# light_detector_v2_3.net
KiCad netlist of a schematic drawn in EAGLE
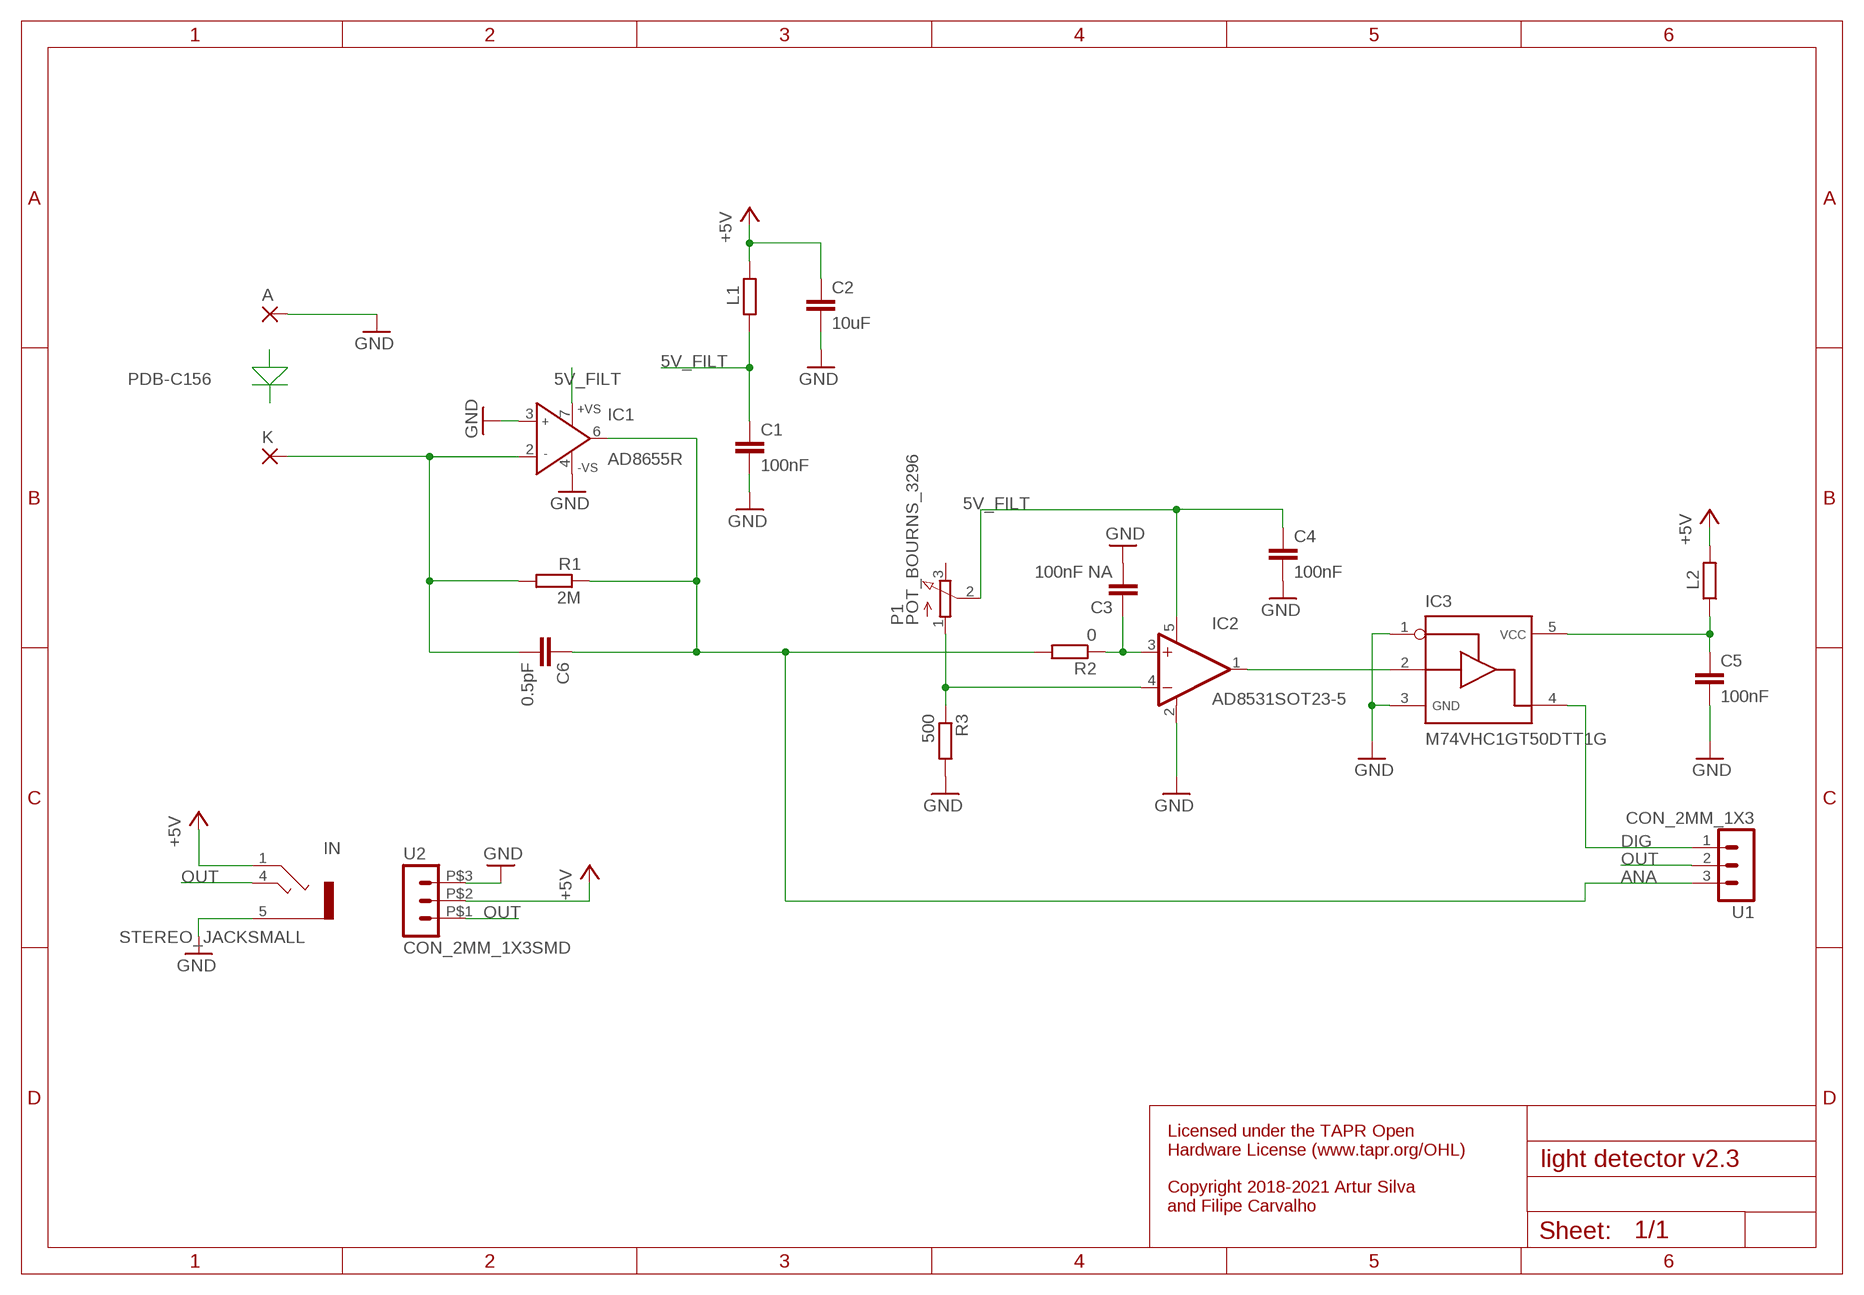
[diagram p0: schematic, sheet 1]

(export (version "E")
  (design (tool "Eeschema 10.0.6"))
  (components
    (comp (ref "A")
      (value "1,6/0,8")
      (footprint "eagle-import:1,6_0,8")
      (libsource (lib "eagle-import") (part "1,6/0,8"))
    )
    (comp (ref "C1")
      (value "100nF")
      (footprint "eagle-import:C0402")
      (libsource (lib "eagle-import") (part "C-EUC0402"))
    )
    (comp (ref "C2")
      (value "10uF")
      (footprint "eagle-import:C0603")
      (libsource (lib "eagle-import") (part "C-EUC0603"))
    )
    (comp (ref "C3")
      (value "100nF NA")
      (footprint "eagle-import:C0402")
      (libsource (lib "eagle-import") (part "C-EUC0402"))
    )
    (comp (ref "C4")
      (value "100nF")
      (footprint "eagle-import:C0402")
      (libsource (lib "eagle-import") (part "C-EUC0402"))
    )
    (comp (ref "C5")
      (value "100nF")
      (footprint "eagle-import:C0402")
      (libsource (lib "eagle-import") (part "C-EUC0402"))
    )
    (comp (ref "C6")
      (value "0.5pF")
      (footprint "eagle-import:C0402")
      (libsource (lib "eagle-import") (part "C-EUC0402"))
    )
    (comp (ref "IC1")
      (value "AD8655R")
      (footprint "eagle-import:SO8")
      (fields (field (name "MF") "ALTERA CORPORATION") (field (name "MPN") "AD8655ARMZ-REEL"))
      (libsource (lib "eagle-import") (part "AD8655R"))
    )
    (comp (ref "IC2")
      (value "AD8531SOT23-5")
      (footprint "eagle-import:SOT23-5")
      (libsource (lib "eagle-import") (part "AD8531SOT23-5"))
    )
    (comp (ref "IC3")
      (value "M74VHC1GT50DTT1G")
      (footprint "eagle-import:SOT23-5")
      (libsource (lib "eagle-import") (part "SN74LVC1G125"))
    )
    (comp (ref "IN")
      (value "STEREO_JACKSMALL")
      (footprint "eagle-import:35RASMT2BHNTRX_")
      (libsource (lib "eagle-import") (part "STEREO_JACKSMALL"))
    )
    (comp (ref "K")
      (value "1,6/0,8")
      (footprint "eagle-import:1,6_0,8")
      (libsource (lib "eagle-import") (part "1,6/0,8"))
    )
    (comp (ref "L1")
      (value "1k@100M")
      (footprint "eagle-import:R0402")
      (libsource (lib "eagle-import") (part "R-EU_R0402"))
    )
    (comp (ref "L2")
      (value "1k@100M")
      (footprint "eagle-import:R0402")
      (libsource (lib "eagle-import") (part "R-EU_R0402"))
    )
    (comp (ref "P1")
      (value "POT_BOURNS_3296")
      (footprint "eagle-import:POT_BOURNS_3296P")
      (libsource (lib "eagle-import") (part "POT_BOURNS_3296"))
    )
    (comp (ref "R1")
      (value "2M")
      (footprint "eagle-import:R0402")
      (libsource (lib "eagle-import") (part "R-EU_R0402"))
    )
    (comp (ref "R2")
      (value "0")
      (footprint "eagle-import:R0402")
      (libsource (lib "eagle-import") (part "R-EU_R0402"))
    )
    (comp (ref "R3")
      (value "500")
      (footprint "eagle-import:R0402")
      (libsource (lib "eagle-import") (part "R-EU_R0402"))
    )
    (comp (ref "U1")
      (value "CON_2MM_1X3")
      (footprint "eagle-import:CON_2MM_1X3")
      (libsource (lib "eagle-import") (part "CON_2MM_1X3"))
    )
    (comp (ref "U2")
      (value "CON_2MM_1X3SMD")
      (footprint "eagle-import:CON_2MM_1X3_SMD")
      (libsource (lib "eagle-import") (part "CON_2MM_1X3SMD"))
    )
  )
  (nets
    (net (code "1") (name "+5V") (class "Default")
      (node (ref "C2") (pin "1") (pinfunction "1_1") (pintype "passive"))
      (node (ref "IN") (pin "1") (pinfunction "1_1") (pintype "passive"))
      (node (ref "L1") (pin "1") (pinfunction "1_1") (pintype "passive"))
      (node (ref "L2") (pin "2") (pinfunction "2_2") (pintype "passive"))
      (node (ref "U2") (pin "P$2") (pinfunction "2_P$2") (pintype "passive"))
    )
    (net (code "2") (name "/5V_FILT") (class "Default")
      (node (ref "C1") (pin "1") (pinfunction "1_1") (pintype "passive"))
      (node (ref "C4") (pin "1") (pinfunction "1_1") (pintype "passive"))
      (node (ref "IC1") (pin "7") (pinfunction "+VS_7") (pintype "input"))
      (node (ref "IC2") (pin "5") (pinfunction "V+_5") (pintype "power_in"))
      (node (ref "L1") (pin "2") (pinfunction "2_2") (pintype "passive"))
      (node (ref "P1") (pin "2") (pinfunction "S_2") (pintype "passive"))
    )
    (net (code "3") (name "/ANA") (class "Default")
      (node (ref "C6") (pin "1") (pinfunction "1_1") (pintype "passive"))
      (node (ref "IC1") (pin "6") (pinfunction "OUT_6") (pintype "output"))
      (node (ref "R1") (pin "1") (pinfunction "1_1") (pintype "passive"))
      (node (ref "R2") (pin "2") (pinfunction "2_2") (pintype "passive"))
      (node (ref "U1") (pin "3") (pinfunction "3_3") (pintype "passive"))
    )
    (net (code "4") (name "/DIG") (class "Default")
      (node (ref "IC3") (pin "4") (pinfunction "P$4_4") (pintype "bidirectional"))
      (node (ref "U1") (pin "1") (pinfunction "1_1") (pintype "passive"))
    )
    (net (code "5") (name "/OUT") (class "Default")
      (node (ref "IN") (pin "4") (pinfunction "4_4") (pintype "passive"))
      (node (ref "U1") (pin "2") (pinfunction "2_2") (pintype "passive"))
      (node (ref "U2") (pin "P$1") (pinfunction "1_P$1") (pintype "passive"))
    )
    (net (code "6") (name "GND") (class "Default")
      (node (ref "A") (pin "1") (pinfunction "P_1") (pintype "passive"))
      (node (ref "C1") (pin "2") (pinfunction "2_2") (pintype "passive"))
      (node (ref "C2") (pin "2") (pinfunction "2_2") (pintype "passive"))
      (node (ref "C3") (pin "2") (pinfunction "2_2") (pintype "passive"))
      (node (ref "C4") (pin "2") (pinfunction "2_2") (pintype "passive"))
      (node (ref "C5") (pin "2") (pinfunction "2_2") (pintype "passive"))
      (node (ref "IC1") (pin "3") (pinfunction "IN+_3") (pintype "input"))
      (node (ref "IC1") (pin "4") (pinfunction "-VS_4") (pintype "input"))
      (node (ref "IC2") (pin "2") (pinfunction "V-_2") (pintype "power_in"))
      (node (ref "IC3") (pin "1") (pinfunction "P$1_1") (pintype "bidirectional"))
      (node (ref "IC3") (pin "3") (pinfunction "P$3_3") (pintype "bidirectional"))
      (node (ref "IN") (pin "5") (pinfunction "5_5") (pintype "passive"))
      (node (ref "R3") (pin "2") (pinfunction "2_2") (pintype "passive"))
      (node (ref "U2") (pin "P$3") (pinfunction "3_P$3") (pintype "passive"))
    )
    (net (code "7") (name "Net-(IC1-IN-)") (class "Default")
      (node (ref "C6") (pin "2") (pinfunction "2_2") (pintype "passive"))
      (node (ref "IC1") (pin "2") (pinfunction "IN-_2") (pintype "input"))
      (node (ref "K") (pin "1") (pinfunction "P_1") (pintype "passive"))
      (node (ref "R1") (pin "2") (pinfunction "2_2") (pintype "passive"))
    )
    (net (code "8") (name "Net-(IC2-+IN)") (class "Default")
      (node (ref "C3") (pin "1") (pinfunction "1_1") (pintype "passive"))
      (node (ref "IC2") (pin "3") (pinfunction "+IN_3") (pintype "input"))
      (node (ref "R2") (pin "1") (pinfunction "1_1") (pintype "passive"))
    )
    (net (code "9") (name "Net-(IC2--IN)") (class "Default")
      (node (ref "IC2") (pin "4") (pinfunction "-IN_4") (pintype "input"))
      (node (ref "P1") (pin "1") (pinfunction "A_1") (pintype "passive"))
      (node (ref "R3") (pin "1") (pinfunction "1_1") (pintype "passive"))
    )
    (net (code "10") (name "Net-(IC2-OUT)") (class "Default")
      (node (ref "IC2") (pin "1") (pinfunction "OUT_1") (pintype "output"))
      (node (ref "IC3") (pin "2") (pinfunction "P$2_2") (pintype "bidirectional"))
    )
    (net (code "11") (name "Net-(IC3-P$5)") (class "Default")
      (node (ref "C5") (pin "1") (pinfunction "1_1") (pintype "passive"))
      (node (ref "IC3") (pin "5") (pinfunction "P$5_5") (pintype "bidirectional"))
      (node (ref "L2") (pin "1") (pinfunction "1_1") (pintype "passive"))
    )
    (net (code "12") (name "unconnected-(P1-E-Pad3)") (class "Default")
      (node (ref "P1") (pin "3") (pinfunction "E_3") (pintype "passive"))
    )
  )
)
